# encoder_se.net
KiCad netlist of a schematic drawn in EAGLE
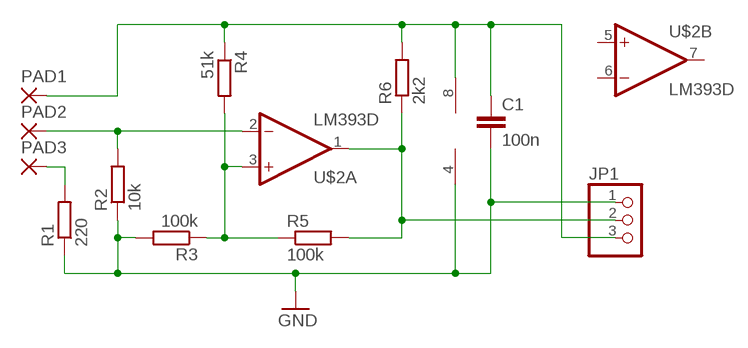
[diagram p0: schematic, sheet 1]

(export (version "E")
  (design (tool "Eeschema 10.0.6"))
  (components
    (comp (ref "C1")
      (value "100n")
      (footprint "eagle-import:C1206")
      (libsource (lib "eagle-import") (part "C-EUC1206"))
    )
    (comp (ref "JP1")
      (value "PINHD-1X3/90")
      (footprint "eagle-import:1X03_90")
      (libsource (lib "eagle-import") (part "PINHD-1X3/90"))
    )
    (comp (ref "PAD1")
      (value "SMD2")
      (footprint "eagle-import:SMD1,27-2,54")
      (libsource (lib "eagle-import") (part "SMD2"))
    )
    (comp (ref "PAD2")
      (value "SMD2")
      (footprint "eagle-import:SMD1,27-2,54")
      (libsource (lib "eagle-import") (part "SMD2"))
    )
    (comp (ref "PAD3")
      (value "SMD2")
      (footprint "eagle-import:SMD1,27-2,54")
      (libsource (lib "eagle-import") (part "SMD2"))
    )
    (comp (ref "R1")
      (value "220")
      (footprint "eagle-import:M1206")
      (libsource (lib "eagle-import") (part "R-EU_M1206"))
    )
    (comp (ref "R2")
      (value "10k")
      (footprint "eagle-import:M1206")
      (libsource (lib "eagle-import") (part "R-EU_M1206"))
    )
    (comp (ref "R3")
      (value "100k")
      (footprint "eagle-import:M1206")
      (libsource (lib "eagle-import") (part "R-EU_M1206"))
    )
    (comp (ref "R4")
      (value "51k")
      (footprint "eagle-import:M1206")
      (libsource (lib "eagle-import") (part "R-EU_M1206"))
    )
    (comp (ref "R5")
      (value "100k")
      (footprint "eagle-import:M1206")
      (libsource (lib "eagle-import") (part "R-EU_M1206"))
    )
    (comp (ref "R6")
      (value "2k2")
      (footprint "eagle-import:M1206")
      (libsource (lib "eagle-import") (part "R-EU_M1206"))
    )
    (comp (ref "U$2")
      (value "LM393D")
      (footprint "eagle-import:SO08")
      (libsource (lib "eagle-import") (part "LM393D"))
    )
  )
  (nets
    (net (code "1") (name "GND") (class "Default")
      (node (ref "C1") (pin "2") (pinfunction "2_2") (pintype "passive"))
      (node (ref "JP1") (pin "1") (pinfunction "1_1") (pintype "passive"))
      (node (ref "R1") (pin "1") (pinfunction "1_1") (pintype "passive"))
      (node (ref "R2") (pin "1") (pinfunction "1_1") (pintype "passive"))
      (node (ref "R3") (pin "2") (pinfunction "2_2") (pintype "passive"))
      (node (ref "U$2") (pin "4") (pinfunction "V-_4") (pintype "power_in"))
    )
    (net (code "2") (name "Net-(PAD1-P)") (class "Default")
      (node (ref "C1") (pin "1") (pinfunction "1_1") (pintype "passive"))
      (node (ref "JP1") (pin "3") (pinfunction "3_3") (pintype "passive"))
      (node (ref "PAD1") (pin "1") (pinfunction "P_1") (pintype "passive"))
      (node (ref "R4") (pin "1") (pinfunction "1_1") (pintype "passive"))
      (node (ref "R6") (pin "2") (pinfunction "2_2") (pintype "passive"))
      (node (ref "U$2") (pin "8") (pinfunction "V+_8") (pintype "power_in"))
    )
    (net (code "3") (name "Net-(PAD2-P)") (class "Default")
      (node (ref "PAD2") (pin "1") (pinfunction "P_1") (pintype "passive"))
      (node (ref "R2") (pin "2") (pinfunction "2_2") (pintype "passive"))
      (node (ref "U$2") (pin "2") (pinfunction "-IN_2") (pintype "input"))
    )
    (net (code "4") (name "Net-(PAD3-P)") (class "Default")
      (node (ref "PAD3") (pin "1") (pinfunction "P_1") (pintype "passive"))
      (node (ref "R1") (pin "2") (pinfunction "2_2") (pintype "passive"))
    )
    (net (code "5") (name "Net-(U$2A-+IN)") (class "Default")
      (node (ref "R3") (pin "1") (pinfunction "1_1") (pintype "passive"))
      (node (ref "R4") (pin "2") (pinfunction "2_2") (pintype "passive"))
      (node (ref "R5") (pin "1") (pinfunction "1_1") (pintype "passive"))
      (node (ref "U$2") (pin "3") (pinfunction "+IN_3") (pintype "input"))
    )
    (net (code "6") (name "Net-(U$2A-OUT)") (class "Default")
      (node (ref "JP1") (pin "2") (pinfunction "2_2") (pintype "passive"))
      (node (ref "R5") (pin "2") (pinfunction "2_2") (pintype "passive"))
      (node (ref "R6") (pin "1") (pinfunction "1_1") (pintype "passive"))
      (node (ref "U$2") (pin "1") (pinfunction "OUT_1") (pintype "output"))
    )
    (net (code "7") (name "unconnected-(U$2B-+IN-Pad5)") (class "Default")
      (node (ref "U$2") (pin "5") (pinfunction "+IN_5") (pintype "input"))
    )
    (net (code "8") (name "unconnected-(U$2B--IN-Pad6)") (class "Default")
      (node (ref "U$2") (pin "6") (pinfunction "-IN_6") (pintype "input"))
    )
    (net (code "9") (name "unconnected-(U$2B-OUT-Pad7)") (class "Default")
      (node (ref "U$2") (pin "7") (pinfunction "OUT_7") (pintype "output"))
    )
  )
)
